# Bluetooth.net
KiCad netlist of a schematic drawn in Altium Designer
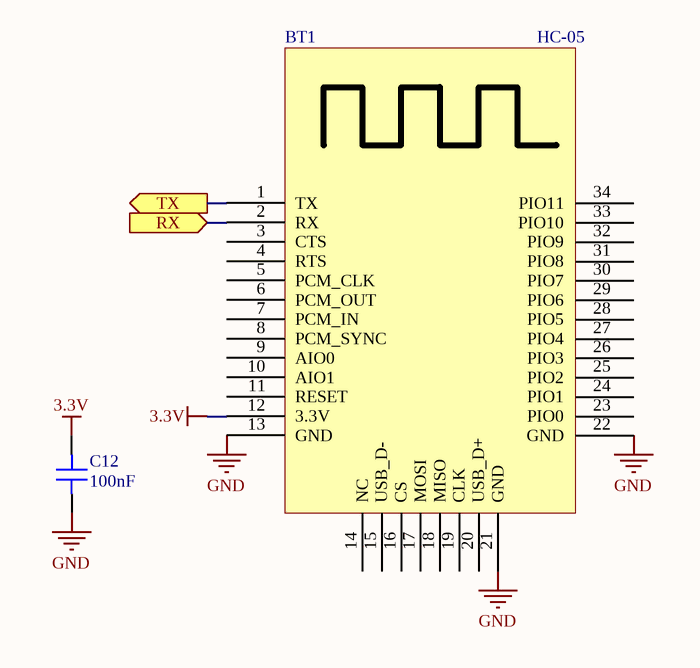
[diagram p0: Bluetooth.SchDoc]

(export (version "E")
  (design (tool "Eeschema 10.0.6"))
  (components
    (comp (ref "BT1") (value "HC-05") (footprint "HC-05") (libsource (lib "Salman_lib") (part "HC-05")))
    (comp (ref "C12")
      (value "100nF")
      (footprint "CAP 0603_1608")
      (description "SMT Capacitor")
      (libsource (lib "Capacitor") (part "Cap 0603"))
    )
  )
  (nets
    (net (code "1") (name "/RX") (class "Default")
      (node (ref "BT1") (pin "2") (pinfunction "RX_2") (pintype "open_emitter"))
    )
    (net (code "2") (name "/TX") (class "Default")
      (node (ref "BT1") (pin "1") (pinfunction "TX_1") (pintype "open_emitter"))
    )
    (net (code "3") (name "3.3V") (class "Default")
      (node (ref "BT1") (pin "12") (pinfunction "3.3V_12") (pintype "open_emitter"))
      (node (ref "C12") (pin "2") (pinfunction "2_2") (pintype "passive"))
    )
    (net (code "4") (name "GND") (class "Default")
      (node (ref "BT1") (pin "13") (pinfunction "GND_13") (pintype "open_emitter"))
      (node (ref "BT1") (pin "21") (pinfunction "GND_21") (pintype "open_emitter"))
      (node (ref "BT1") (pin "22") (pinfunction "GND_22") (pintype "open_emitter"))
      (node (ref "C12") (pin "1") (pinfunction "1_1") (pintype "passive"))
    )
    (net (code "5") (name "unconnected-(BT1-AIO0-Pad9)") (class "Default")
      (node (ref "BT1") (pin "9") (pinfunction "AIO0_9") (pintype "open_emitter"))
    )
    (net (code "6") (name "unconnected-(BT1-AIO1-Pad10)") (class "Default")
      (node (ref "BT1") (pin "10") (pinfunction "AIO1_10") (pintype "open_emitter"))
    )
    (net (code "7") (name "unconnected-(BT1-CLK-Pad19)") (class "Default")
      (node (ref "BT1") (pin "19") (pinfunction "CLK_19") (pintype "open_emitter"))
    )
    (net (code "8") (name "unconnected-(BT1-CS-Pad16)") (class "Default")
      (node (ref "BT1") (pin "16") (pinfunction "CS_16") (pintype "open_emitter"))
    )
    (net (code "9") (name "unconnected-(BT1-CTS-Pad3)") (class "Default")
      (node (ref "BT1") (pin "3") (pinfunction "CTS_3") (pintype "open_emitter"))
    )
    (net (code "10") (name "unconnected-(BT1-MISO-Pad18)") (class "Default")
      (node (ref "BT1") (pin "18") (pinfunction "MISO_18") (pintype "open_emitter"))
    )
    (net (code "11") (name "unconnected-(BT1-MOSI-Pad17)") (class "Default")
      (node (ref "BT1") (pin "17") (pinfunction "MOSI_17") (pintype "open_emitter"))
    )
    (net (code "12") (name "unconnected-(BT1-NC-Pad14)") (class "Default")
      (node (ref "BT1") (pin "14") (pinfunction "NC_14") (pintype "open_emitter"))
    )
    (net (code "13") (name "unconnected-(BT1-PCM_CLK-Pad5)") (class "Default")
      (node (ref "BT1") (pin "5") (pinfunction "PCM_CLK_5") (pintype "open_emitter"))
    )
    (net (code "14") (name "unconnected-(BT1-PCM_IN-Pad7)") (class "Default")
      (node (ref "BT1") (pin "7") (pinfunction "PCM_IN_7") (pintype "open_emitter"))
    )
    (net (code "15") (name "unconnected-(BT1-PCM_OUT-Pad6)") (class "Default")
      (node (ref "BT1") (pin "6") (pinfunction "PCM_OUT_6") (pintype "open_emitter"))
    )
    (net (code "16") (name "unconnected-(BT1-PCM_SYNC-Pad8)") (class "Default")
      (node (ref "BT1") (pin "8") (pinfunction "PCM_SYNC_8") (pintype "open_emitter"))
    )
    (net (code "17") (name "unconnected-(BT1-PIO0-Pad23)") (class "Default")
      (node (ref "BT1") (pin "23") (pinfunction "PIO0_23") (pintype "open_emitter"))
    )
    (net (code "18") (name "unconnected-(BT1-PIO1-Pad24)") (class "Default")
      (node (ref "BT1") (pin "24") (pinfunction "PIO1_24") (pintype "open_emitter"))
    )
    (net (code "19") (name "unconnected-(BT1-PIO2-Pad25)") (class "Default")
      (node (ref "BT1") (pin "25") (pinfunction "PIO2_25") (pintype "open_emitter"))
    )
    (net (code "20") (name "unconnected-(BT1-PIO3-Pad26)") (class "Default")
      (node (ref "BT1") (pin "26") (pinfunction "PIO3_26") (pintype "open_emitter"))
    )
    (net (code "21") (name "unconnected-(BT1-PIO4-Pad27)") (class "Default")
      (node (ref "BT1") (pin "27") (pinfunction "PIO4_27") (pintype "open_emitter"))
    )
    (net (code "22") (name "unconnected-(BT1-PIO5-Pad28)") (class "Default")
      (node (ref "BT1") (pin "28") (pinfunction "PIO5_28") (pintype "open_emitter"))
    )
    (net (code "23") (name "unconnected-(BT1-PIO6-Pad29)") (class "Default")
      (node (ref "BT1") (pin "29") (pinfunction "PIO6_29") (pintype "open_emitter"))
    )
    (net (code "24") (name "unconnected-(BT1-PIO7-Pad30)") (class "Default")
      (node (ref "BT1") (pin "30") (pinfunction "PIO7_30") (pintype "open_emitter"))
    )
    (net (code "25") (name "unconnected-(BT1-PIO8-Pad31)") (class "Default")
      (node (ref "BT1") (pin "31") (pinfunction "PIO8_31") (pintype "open_emitter"))
    )
    (net (code "26") (name "unconnected-(BT1-PIO9-Pad32)") (class "Default")
      (node (ref "BT1") (pin "32") (pinfunction "PIO9_32") (pintype "open_emitter"))
    )
    (net (code "27") (name "unconnected-(BT1-PIO10-Pad33)") (class "Default")
      (node (ref "BT1") (pin "33") (pinfunction "PIO10_33") (pintype "open_emitter"))
    )
    (net (code "28") (name "unconnected-(BT1-PIO11-Pad34)") (class "Default")
      (node (ref "BT1") (pin "34") (pinfunction "PIO11_34") (pintype "open_emitter"))
    )
    (net (code "29") (name "unconnected-(BT1-RESET-Pad11)") (class "Default")
      (node (ref "BT1") (pin "11") (pinfunction "RESET_11") (pintype "open_emitter"))
    )
    (net (code "30") (name "unconnected-(BT1-RTS-Pad4)") (class "Default")
      (node (ref "BT1") (pin "4") (pinfunction "RTS_4") (pintype "open_emitter"))
    )
    (net (code "31") (name "unconnected-(BT1-USB_D+-Pad20)") (class "Default")
      (node (ref "BT1") (pin "20") (pinfunction "USB_D+_20") (pintype "open_emitter"))
    )
    (net (code "32") (name "unconnected-(BT1-USB_D--Pad15)") (class "Default")
      (node (ref "BT1") (pin "15") (pinfunction "USB_D-_15") (pintype "open_emitter"))
    )
  )
)
